# Sensor.net
KiCad netlist of a schematic drawn in EAGLE
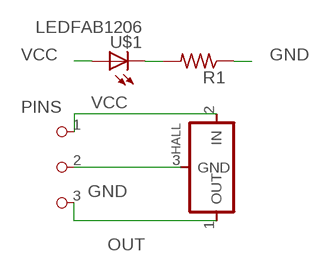
[diagram p0: schematic, sheet 1]

(export (version "E")
  (design (tool "Eeschema 10.0.6"))
  (components
    (comp (ref "HALL")
      (value "REGULATORSOT23")
      (footprint "eagle-import:SOT23")
      (libsource (lib "eagle-import") (part "REGULATORSOT23"))
    )
    (comp (ref "PINS")
      (value "SPDTSWITCH")
      (footprint "eagle-import:SPDTSWITCH")
      (libsource (lib "eagle-import") (part "SPDTSWITCH"))
    )
    (comp (ref "R1")
      (value "RES-US1206FAB")
      (footprint "eagle-import:R1206FAB")
      (libsource (lib "eagle-import") (part "RES-US1206FAB"))
    )
    (comp (ref "U$1")
      (value "LEDFAB1206")
      (footprint "eagle-import:LED1206FAB")
      (libsource (lib "eagle-import") (part "LEDFAB1206"))
    )
  )
  (nets
    (net (code "1") (name "/GND") (class "Default")
      (node (ref "HALL") (pin "3") (pinfunction "GND_3") (pintype "bidirectional"))
      (node (ref "PINS") (pin "2") (pinfunction "2_2") (pintype "passive"))
      (node (ref "R1") (pin "1") (pinfunction "1_1") (pintype "passive"))
    )
    (net (code "2") (name "/OUT") (class "Default")
      (node (ref "HALL") (pin "1") (pinfunction "OUT_1") (pintype "bidirectional"))
      (node (ref "PINS") (pin "3") (pinfunction "3_3") (pintype "passive"))
    )
    (net (code "3") (name "/VCC") (class "Default")
      (node (ref "HALL") (pin "2") (pinfunction "IN_2") (pintype "bidirectional"))
      (node (ref "PINS") (pin "1") (pinfunction "1_1") (pintype "passive"))
      (node (ref "U$1") (pin "1") (pinfunction "A_1") (pintype "passive"))
    )
    (net (code "4") (name "Net-(U$1-C)") (class "Default")
      (node (ref "R1") (pin "2") (pinfunction "2_2") (pintype "passive"))
      (node (ref "U$1") (pin "2") (pinfunction "C_2") (pintype "passive"))
    )
  )
)
